# Sheet2.net
KiCad netlist of a schematic drawn in Altium Designer
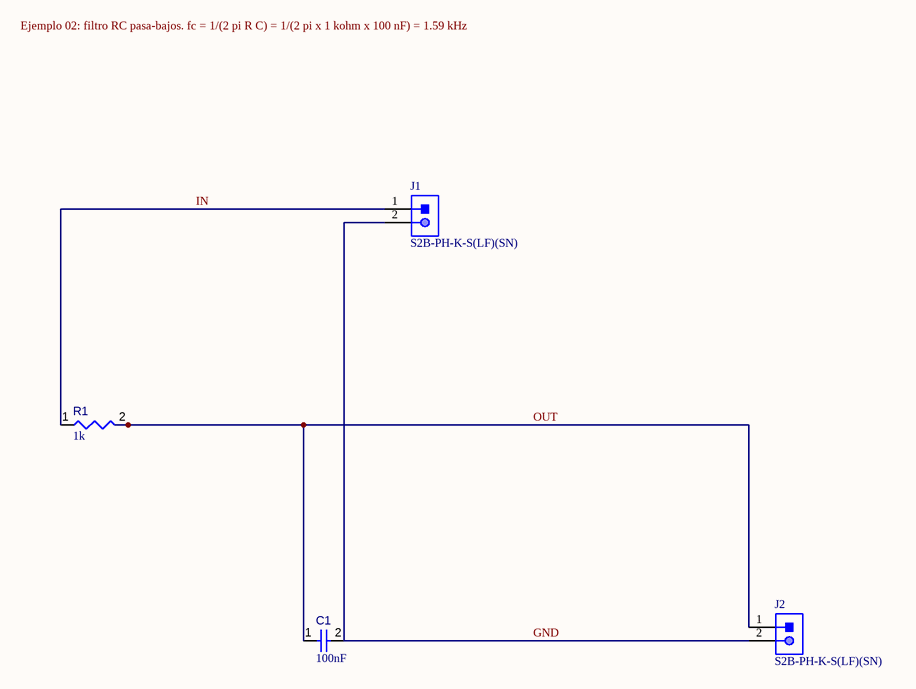
[diagram p0: Sheet2.SchDoc]

(export (version "E")
  (design (tool "Eeschema 10.0.6"))
  (components
    (comp (ref "C1")
      (value "100nF")
      (footprint "CAPC0402(1005)60_L")
      (description "Chip Capacitor, 100nF +/-20%, 25V, 0402, Thickness 0.6 mm")
      (fields (field (name "TOLERANCE") "10%") (field (name "Comment") "Capacitor 100nF +/-20% 25V 0402"))
      (libsource (lib "EFRAIN ALVARADO") (part "CAP-NP-2"))
    )
    (comp (ref "J1")
      (value "S2B-PH-K-S(LF)(SN)")
      (footprint "JST-S2B-PH-K-S_V")
      (fields (field (name "MANUFACTURER") "Japan Solderless Terminals"))
      (libsource (lib "EFRAIN ALVARADO") (part "CN-1P-M-R2"))
    )
    (comp (ref "J2")
      (value "S2B-PH-K-S(LF)(SN)")
      (footprint "JST-S2B-PH-K-S_V")
      (fields (field (name "MANUFACTURER") "Japan Solderless Terminals"))
      (libsource (lib "EFRAIN ALVARADO") (part "CN-1P-M-R2"))
    )
    (comp (ref "R1")
      (value "1k")
      (footprint "RESC0402(1005)_L")
      (description "1K 0.063W 5% 0402 (1005 Metric)  SMD")
      (fields (field (name "POWER") "63mW") (field (name "TOLERANCE") "5%"))
      (libsource (lib "EFRAIN ALVARADO") (part "1KR2J"))
    )
  )
  (nets
    (net (code "1") (name "/GND") (class "Default")
      (node (ref "C1") (pin "2") (pinfunction "2_2") (pintype "passive"))
      (node (ref "J1") (pin "2") (pinfunction "2_2") (pintype "passive"))
      (node (ref "J2") (pin "2") (pinfunction "2_2") (pintype "passive"))
    )
    (net (code "2") (name "/IN") (class "Default")
      (node (ref "J1") (pin "1") (pinfunction "1_1") (pintype "passive"))
      (node (ref "R1") (pin "1") (pinfunction "1_1") (pintype "passive"))
    )
    (net (code "3") (name "/OUT") (class "Default")
      (node (ref "C1") (pin "1") (pinfunction "1_1") (pintype "passive"))
      (node (ref "J2") (pin "1") (pinfunction "1_1") (pintype "passive"))
      (node (ref "R1") (pin "2") (pinfunction "2_2") (pintype "passive"))
    )
  )
)
